# DDR3L.net
KiCad netlist of a schematic drawn in Altium Designer
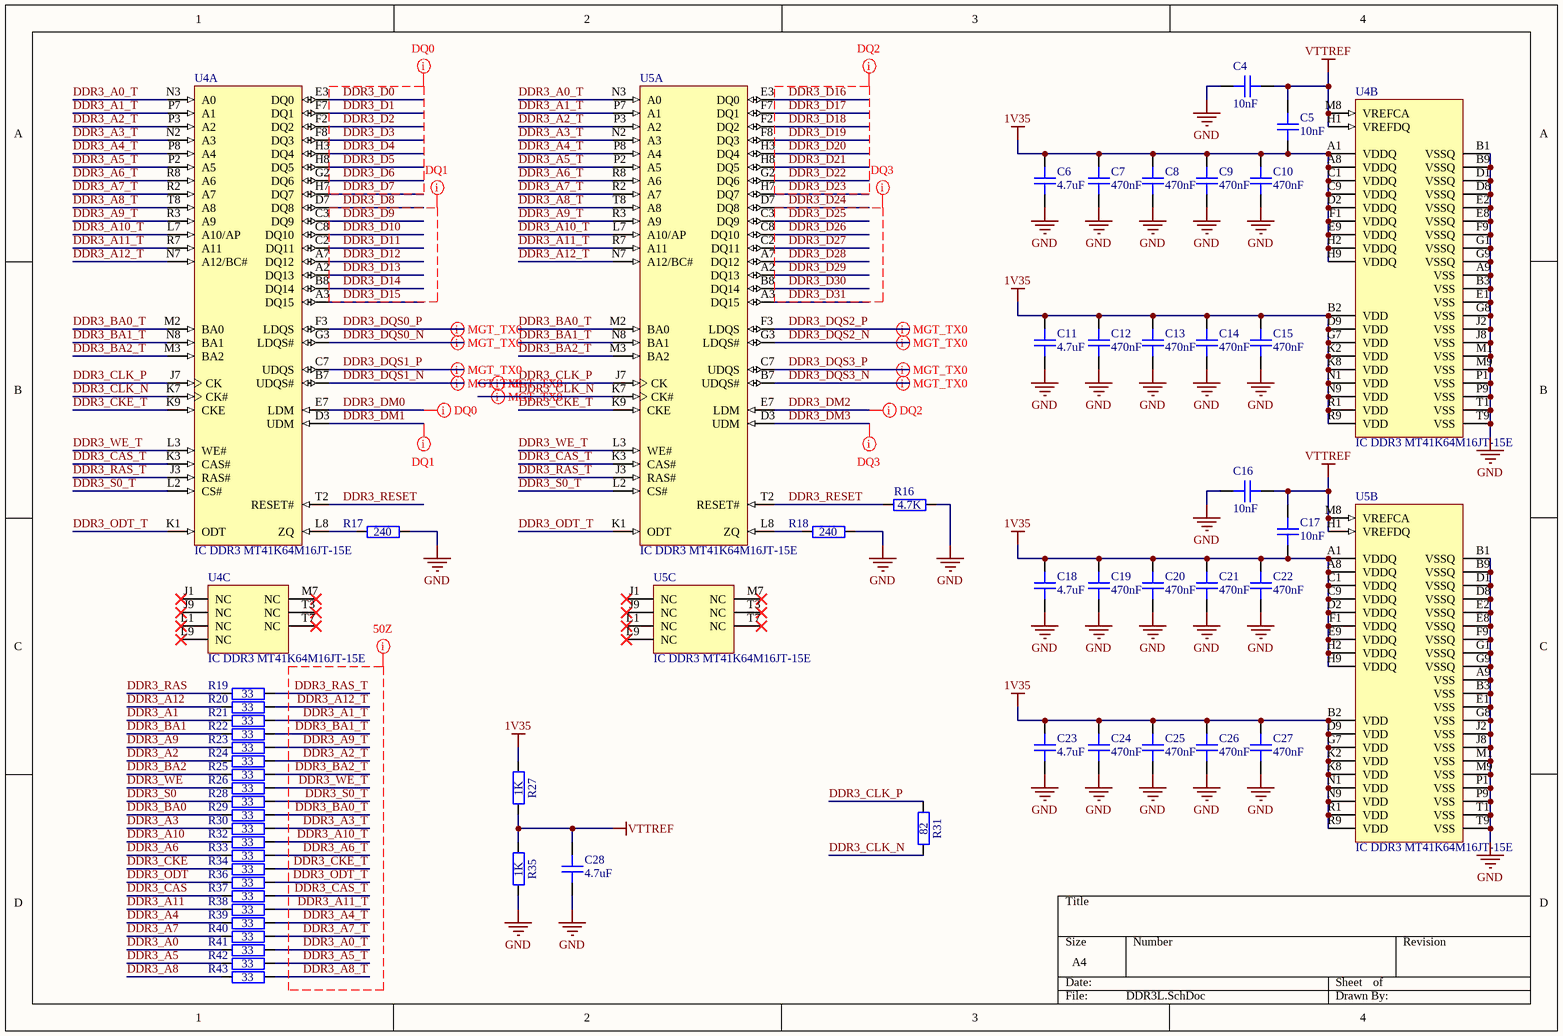
[diagram p0: DDR3L.SchDoc]

(export (version "E")
  (design (tool "Eeschema 10.0.6"))
  (components
    (comp (ref "C4")
      (value "10nF")
      (footprint "GEN_C_0402")
      (fields
        (field (name "HOUSE PART NUMBER") "C-10nF-0402-002")
        (field (name "MANUFACTURER") "Murata")
        (field (name "MANUFACTURER PART NUMBER") "GRM155R71H103KA88J")
      )
      (libsource (lib "DSO") (part "CAP 10nF 50V X7R 0402"))
    )
    (comp (ref "C5")
      (value "10nF")
      (footprint "GEN_C_0402")
      (fields
        (field (name "HOUSE PART NUMBER") "C-10nF-0402-002")
        (field (name "MANUFACTURER") "Murata")
        (field (name "MANUFACTURER PART NUMBER") "GRM155R71H103KA88J")
      )
      (libsource (lib "DSO") (part "CAP 10nF 50V X7R 0402"))
    )
    (comp (ref "C6")
      (value "4.7uF")
      (footprint "GEN_C_0402")
      (fields
        (field (name "HOUSE PART NUMBER") "C-4.7uF-0402-002")
        (field (name "MANUFACTURER") "Murata")
        (field (name "MANUFACTURER PART NUMBER") "GRM155R60J475ME47D")
      )
      (libsource (lib "DSO") (part "CAP 4.7uF 6.3V X5R 0402"))
    )
    (comp (ref "C7")
      (value "470nF")
      (footprint "GEN_C_0201")
      (fields
        (field (name "HOUSE PART NUMBER") "C-470nF-0201-002")
        (field (name "MANUFACTURER") "Murata")
        (field (name "MANUFACTURER PART NUMBER") "GRM033R60J474KE90D")
      )
      (libsource (lib "DSO") (part "CAP 470nF 6.3V X5R 0201"))
    )
    (comp (ref "C8")
      (value "470nF")
      (footprint "GEN_C_0201")
      (fields
        (field (name "HOUSE PART NUMBER") "C-470nF-0201-002")
        (field (name "MANUFACTURER") "Murata")
        (field (name "MANUFACTURER PART NUMBER") "GRM033R60J474KE90D")
      )
      (libsource (lib "DSO") (part "CAP 470nF 6.3V X5R 0201"))
    )
    (comp (ref "C9")
      (value "470nF")
      (footprint "GEN_C_0201")
      (fields
        (field (name "HOUSE PART NUMBER") "C-470nF-0201-002")
        (field (name "MANUFACTURER") "Murata")
        (field (name "MANUFACTURER PART NUMBER") "GRM033R60J474KE90D")
      )
      (libsource (lib "DSO") (part "CAP 470nF 6.3V X5R 0201"))
    )
    (comp (ref "C10")
      (value "470nF")
      (footprint "GEN_C_0201")
      (fields
        (field (name "HOUSE PART NUMBER") "C-470nF-0201-002")
        (field (name "MANUFACTURER") "Murata")
        (field (name "MANUFACTURER PART NUMBER") "GRM033R60J474KE90D")
      )
      (libsource (lib "DSO") (part "CAP 470nF 6.3V X5R 0201"))
    )
    (comp (ref "C11")
      (value "4.7uF")
      (footprint "GEN_C_0402")
      (fields
        (field (name "HOUSE PART NUMBER") "C-4.7uF-0402-002")
        (field (name "MANUFACTURER") "Murata")
        (field (name "MANUFACTURER PART NUMBER") "GRM155R60J475ME47D")
      )
      (libsource (lib "DSO") (part "CAP 4.7uF 6.3V X5R 0402"))
    )
    (comp (ref "C12")
      (value "470nF")
      (footprint "GEN_C_0201")
      (fields
        (field (name "HOUSE PART NUMBER") "C-470nF-0201-002")
        (field (name "MANUFACTURER") "Murata")
        (field (name "MANUFACTURER PART NUMBER") "GRM033R60J474KE90D")
      )
      (libsource (lib "DSO") (part "CAP 470nF 6.3V X5R 0201"))
    )
    (comp (ref "C13")
      (value "470nF")
      (footprint "GEN_C_0201")
      (fields
        (field (name "HOUSE PART NUMBER") "C-470nF-0201-002")
        (field (name "MANUFACTURER") "Murata")
        (field (name "MANUFACTURER PART NUMBER") "GRM033R60J474KE90D")
      )
      (libsource (lib "DSO") (part "CAP 470nF 6.3V X5R 0201"))
    )
    (comp (ref "C14")
      (value "470nF")
      (footprint "GEN_C_0201")
      (fields
        (field (name "HOUSE PART NUMBER") "C-470nF-0201-002")
        (field (name "MANUFACTURER") "Murata")
        (field (name "MANUFACTURER PART NUMBER") "GRM033R60J474KE90D")
      )
      (libsource (lib "DSO") (part "CAP 470nF 6.3V X5R 0201"))
    )
    (comp (ref "C15")
      (value "470nF")
      (footprint "GEN_C_0201")
      (fields
        (field (name "HOUSE PART NUMBER") "C-470nF-0201-002")
        (field (name "MANUFACTURER") "Murata")
        (field (name "MANUFACTURER PART NUMBER") "GRM033R60J474KE90D")
      )
      (libsource (lib "DSO") (part "CAP 470nF 6.3V X5R 0201"))
    )
    (comp (ref "C16")
      (value "10nF")
      (footprint "GEN_C_0402")
      (fields
        (field (name "HOUSE PART NUMBER") "C-10nF-0402-002")
        (field (name "MANUFACTURER") "Murata")
        (field (name "MANUFACTURER PART NUMBER") "GRM155R71H103KA88J")
      )
      (libsource (lib "DSO") (part "CAP 10nF 50V X7R 0402"))
    )
    (comp (ref "C17")
      (value "10nF")
      (footprint "GEN_C_0402")
      (fields
        (field (name "HOUSE PART NUMBER") "C-10nF-0402-002")
        (field (name "MANUFACTURER") "Murata")
        (field (name "MANUFACTURER PART NUMBER") "GRM155R71H103KA88J")
      )
      (libsource (lib "DSO") (part "CAP 10nF 50V X7R 0402"))
    )
    (comp (ref "C18")
      (value "4.7uF")
      (footprint "GEN_C_0402")
      (fields
        (field (name "HOUSE PART NUMBER") "C-4.7uF-0402-002")
        (field (name "MANUFACTURER") "Murata")
        (field (name "MANUFACTURER PART NUMBER") "GRM155R60J475ME47D")
      )
      (libsource (lib "DSO") (part "CAP 4.7uF 6.3V X5R 0402"))
    )
    (comp (ref "C19")
      (value "470nF")
      (footprint "GEN_C_0201")
      (fields
        (field (name "HOUSE PART NUMBER") "C-470nF-0201-002")
        (field (name "MANUFACTURER") "Murata")
        (field (name "MANUFACTURER PART NUMBER") "GRM033R60J474KE90D")
      )
      (libsource (lib "DSO") (part "CAP 470nF 6.3V X5R 0201"))
    )
    (comp (ref "C20")
      (value "470nF")
      (footprint "GEN_C_0201")
      (fields
        (field (name "HOUSE PART NUMBER") "C-470nF-0201-002")
        (field (name "MANUFACTURER") "Murata")
        (field (name "MANUFACTURER PART NUMBER") "GRM033R60J474KE90D")
      )
      (libsource (lib "DSO") (part "CAP 470nF 6.3V X5R 0201"))
    )
    (comp (ref "C21")
      (value "470nF")
      (footprint "GEN_C_0201")
      (fields
        (field (name "HOUSE PART NUMBER") "C-470nF-0201-002")
        (field (name "MANUFACTURER") "Murata")
        (field (name "MANUFACTURER PART NUMBER") "GRM033R60J474KE90D")
      )
      (libsource (lib "DSO") (part "CAP 470nF 6.3V X5R 0201"))
    )
    (comp (ref "C22")
      (value "470nF")
      (footprint "GEN_C_0201")
      (fields
        (field (name "HOUSE PART NUMBER") "C-470nF-0201-002")
        (field (name "MANUFACTURER") "Murata")
        (field (name "MANUFACTURER PART NUMBER") "GRM033R60J474KE90D")
      )
      (libsource (lib "DSO") (part "CAP 470nF 6.3V X5R 0201"))
    )
    (comp (ref "C23")
      (value "4.7uF")
      (footprint "GEN_C_0402")
      (fields
        (field (name "HOUSE PART NUMBER") "C-4.7uF-0402-002")
        (field (name "MANUFACTURER") "Murata")
        (field (name "MANUFACTURER PART NUMBER") "GRM155R60J475ME47D")
      )
      (libsource (lib "DSO") (part "CAP 4.7uF 6.3V X5R 0402"))
    )
    (comp (ref "C24")
      (value "470nF")
      (footprint "GEN_C_0201")
      (fields
        (field (name "HOUSE PART NUMBER") "C-470nF-0201-002")
        (field (name "MANUFACTURER") "Murata")
        (field (name "MANUFACTURER PART NUMBER") "GRM033R60J474KE90D")
      )
      (libsource (lib "DSO") (part "CAP 470nF 6.3V X5R 0201"))
    )
    (comp (ref "C25")
      (value "470nF")
      (footprint "GEN_C_0201")
      (fields
        (field (name "HOUSE PART NUMBER") "C-470nF-0201-002")
        (field (name "MANUFACTURER") "Murata")
        (field (name "MANUFACTURER PART NUMBER") "GRM033R60J474KE90D")
      )
      (libsource (lib "DSO") (part "CAP 470nF 6.3V X5R 0201"))
    )
    (comp (ref "C26")
      (value "470nF")
      (footprint "GEN_C_0201")
      (fields
        (field (name "HOUSE PART NUMBER") "C-470nF-0201-002")
        (field (name "MANUFACTURER") "Murata")
        (field (name "MANUFACTURER PART NUMBER") "GRM033R60J474KE90D")
      )
      (libsource (lib "DSO") (part "CAP 470nF 6.3V X5R 0201"))
    )
    (comp (ref "C27")
      (value "470nF")
      (footprint "GEN_C_0201")
      (fields
        (field (name "HOUSE PART NUMBER") "C-470nF-0201-002")
        (field (name "MANUFACTURER") "Murata")
        (field (name "MANUFACTURER PART NUMBER") "GRM033R60J474KE90D")
      )
      (libsource (lib "DSO") (part "CAP 470nF 6.3V X5R 0201"))
    )
    (comp (ref "C28")
      (value "4.7uF")
      (footprint "GEN_C_0402")
      (fields
        (field (name "HOUSE PART NUMBER") "C-4.7uF-0402-002")
        (field (name "MANUFACTURER") "Murata")
        (field (name "MANUFACTURER PART NUMBER") "GRM155R60J475ME47D")
      )
      (libsource (lib "DSO") (part "CAP 4.7uF 6.3V X5R 0402"))
    )
    (comp (ref "R16")
      (value "4.7K")
      (footprint "GEN_R_0201")
      (fields
        (field (name "TOLERANCE") "1%")
        (field (name "HOUSE PART NUMBER") "R-4.7K-0201-1%-001")
        (field (name "MANUFACTURER") "Yageo")
      )
      (libsource (lib "DSO") (part "RES 4.7K OHM 1% 1/20W 0201"))
    )
    (comp (ref "R17")
      (value "240")
      (footprint "GEN_R_0402")
      (fields
        (field (name "TOLERANCE") "1%")
        (field (name "HOUSE PART NUMBER") "R-240-0402-1%-001")
        (field (name "MANUFACTURER") "Yageo")
      )
      (libsource (lib "DSO") (part "RES 240 OHM 1% 1/16W 0402"))
    )
    (comp (ref "R18")
      (value "240")
      (footprint "GEN_R_0402")
      (fields
        (field (name "TOLERANCE") "1%")
        (field (name "HOUSE PART NUMBER") "R-240-0402-1%-001")
        (field (name "MANUFACTURER") "Yageo")
      )
      (libsource (lib "DSO") (part "RES 240 OHM 1% 1/16W 0402"))
    )
    (comp (ref "R19")
      (value "33")
      (footprint "GEN_R_0201")
      (fields
        (field (name "TOLERANCE") "1%")
        (field (name "HOUSE PART NUMBER") "R-33-0201-1%-001")
        (field (name "MANUFACTURER") "Stackpole Electronics")
      )
      (libsource (lib "DSO") (part "RES 33 OHM 1% 1/20W 0201"))
    )
    (comp (ref "R20")
      (value "33")
      (footprint "GEN_R_0201")
      (fields
        (field (name "TOLERANCE") "1%")
        (field (name "HOUSE PART NUMBER") "R-33-0201-1%-001")
        (field (name "MANUFACTURER") "Stackpole Electronics")
      )
      (libsource (lib "DSO") (part "RES 33 OHM 1% 1/20W 0201"))
    )
    (comp (ref "R21")
      (value "33")
      (footprint "GEN_R_0201")
      (fields
        (field (name "TOLERANCE") "1%")
        (field (name "HOUSE PART NUMBER") "R-33-0201-1%-001")
        (field (name "MANUFACTURER") "Stackpole Electronics")
      )
      (libsource (lib "DSO") (part "RES 33 OHM 1% 1/20W 0201"))
    )
    (comp (ref "R22")
      (value "33")
      (footprint "GEN_R_0201")
      (fields
        (field (name "TOLERANCE") "1%")
        (field (name "HOUSE PART NUMBER") "R-33-0201-1%-001")
        (field (name "MANUFACTURER") "Stackpole Electronics")
      )
      (libsource (lib "DSO") (part "RES 33 OHM 1% 1/20W 0201"))
    )
    (comp (ref "R23")
      (value "33")
      (footprint "GEN_R_0201")
      (fields
        (field (name "TOLERANCE") "1%")
        (field (name "HOUSE PART NUMBER") "R-33-0201-1%-001")
        (field (name "MANUFACTURER") "Stackpole Electronics")
      )
      (libsource (lib "DSO") (part "RES 33 OHM 1% 1/20W 0201"))
    )
    (comp (ref "R24")
      (value "33")
      (footprint "GEN_R_0201")
      (fields
        (field (name "TOLERANCE") "1%")
        (field (name "HOUSE PART NUMBER") "R-33-0201-1%-001")
        (field (name "MANUFACTURER") "Stackpole Electronics")
      )
      (libsource (lib "DSO") (part "RES 33 OHM 1% 1/20W 0201"))
    )
    (comp (ref "R25")
      (value "33")
      (footprint "GEN_R_0201")
      (fields
        (field (name "TOLERANCE") "1%")
        (field (name "HOUSE PART NUMBER") "R-33-0201-1%-001")
        (field (name "MANUFACTURER") "Stackpole Electronics")
      )
      (libsource (lib "DSO") (part "RES 33 OHM 1% 1/20W 0201"))
    )
    (comp (ref "R26")
      (value "33")
      (footprint "GEN_R_0201")
      (fields
        (field (name "TOLERANCE") "1%")
        (field (name "HOUSE PART NUMBER") "R-33-0201-1%-001")
        (field (name "MANUFACTURER") "Stackpole Electronics")
      )
      (libsource (lib "DSO") (part "RES 33 OHM 1% 1/20W 0201"))
    )
    (comp (ref "R27")
      (value "1K")
      (footprint "GEN_R_0402")
      (fields
        (field (name "TOLERANCE") "1%")
        (field (name "HOUSE PART NUMBER") "R-1K-0402-1%-001")
        (field (name "MANUFACTURER") "Yageo")
      )
      (libsource (lib "DSO") (part "RES 1K OHM 1% 1/10W 0402"))
    )
    (comp (ref "R28")
      (value "33")
      (footprint "GEN_R_0201")
      (fields
        (field (name "TOLERANCE") "1%")
        (field (name "HOUSE PART NUMBER") "R-33-0201-1%-001")
        (field (name "MANUFACTURER") "Stackpole Electronics")
      )
      (libsource (lib "DSO") (part "RES 33 OHM 1% 1/20W 0201"))
    )
    (comp (ref "R29")
      (value "33")
      (footprint "GEN_R_0201")
      (fields
        (field (name "TOLERANCE") "1%")
        (field (name "HOUSE PART NUMBER") "R-33-0201-1%-001")
        (field (name "MANUFACTURER") "Stackpole Electronics")
      )
      (libsource (lib "DSO") (part "RES 33 OHM 1% 1/20W 0201"))
    )
    (comp (ref "R30")
      (value "33")
      (footprint "GEN_R_0201")
      (fields
        (field (name "TOLERANCE") "1%")
        (field (name "HOUSE PART NUMBER") "R-33-0201-1%-001")
        (field (name "MANUFACTURER") "Stackpole Electronics")
      )
      (libsource (lib "DSO") (part "RES 33 OHM 1% 1/20W 0201"))
    )
    (comp (ref "R31")
      (value "82")
      (footprint "GEN_R_0402")
      (fields
        (field (name "TOLERANCE") "1%")
        (field (name "HOUSE PART NUMBER") "R-82-0402-1%-001")
        (field (name "MANUFACTURER") "Yageo")
      )
      (libsource (lib "DSO") (part "RES 82 OHM 1% 1/16W 0402"))
    )
    (comp (ref "R32")
      (value "33")
      (footprint "GEN_R_0201")
      (fields
        (field (name "TOLERANCE") "1%")
        (field (name "HOUSE PART NUMBER") "R-33-0201-1%-001")
        (field (name "MANUFACTURER") "Stackpole Electronics")
      )
      (libsource (lib "DSO") (part "RES 33 OHM 1% 1/20W 0201"))
    )
    (comp (ref "R33")
      (value "33")
      (footprint "GEN_R_0201")
      (fields
        (field (name "TOLERANCE") "1%")
        (field (name "HOUSE PART NUMBER") "R-33-0201-1%-001")
        (field (name "MANUFACTURER") "Stackpole Electronics")
      )
      (libsource (lib "DSO") (part "RES 33 OHM 1% 1/20W 0201"))
    )
    (comp (ref "R34")
      (value "33")
      (footprint "GEN_R_0201")
      (fields
        (field (name "TOLERANCE") "1%")
        (field (name "HOUSE PART NUMBER") "R-33-0201-1%-001")
        (field (name "MANUFACTURER") "Stackpole Electronics")
      )
      (libsource (lib "DSO") (part "RES 33 OHM 1% 1/20W 0201"))
    )
    (comp (ref "R35")
      (value "1K")
      (footprint "GEN_R_0402")
      (fields
        (field (name "TOLERANCE") "1%")
        (field (name "HOUSE PART NUMBER") "R-1K-0402-1%-001")
        (field (name "MANUFACTURER") "Yageo")
      )
      (libsource (lib "DSO") (part "RES 1K OHM 1% 1/10W 0402"))
    )
    (comp (ref "R36")
      (value "33")
      (footprint "GEN_R_0201")
      (fields
        (field (name "TOLERANCE") "1%")
        (field (name "HOUSE PART NUMBER") "R-33-0201-1%-001")
        (field (name "MANUFACTURER") "Stackpole Electronics")
      )
      (libsource (lib "DSO") (part "RES 33 OHM 1% 1/20W 0201"))
    )
    (comp (ref "R37")
      (value "33")
      (footprint "GEN_R_0201")
      (fields
        (field (name "TOLERANCE") "1%")
        (field (name "HOUSE PART NUMBER") "R-33-0201-1%-001")
        (field (name "MANUFACTURER") "Stackpole Electronics")
      )
      (libsource (lib "DSO") (part "RES 33 OHM 1% 1/20W 0201"))
    )
    (comp (ref "R38")
      (value "33")
      (footprint "GEN_R_0201")
      (fields
        (field (name "TOLERANCE") "1%")
        (field (name "HOUSE PART NUMBER") "R-33-0201-1%-001")
        (field (name "MANUFACTURER") "Stackpole Electronics")
      )
      (libsource (lib "DSO") (part "RES 33 OHM 1% 1/20W 0201"))
    )
    (comp (ref "R39")
      (value "33")
      (footprint "GEN_R_0201")
      (fields
        (field (name "TOLERANCE") "1%")
        (field (name "HOUSE PART NUMBER") "R-33-0201-1%-001")
        (field (name "MANUFACTURER") "Stackpole Electronics")
      )
      (libsource (lib "DSO") (part "RES 33 OHM 1% 1/20W 0201"))
    )
    (comp (ref "R40")
      (value "33")
      (footprint "GEN_R_0201")
      (fields
        (field (name "TOLERANCE") "1%")
        (field (name "HOUSE PART NUMBER") "R-33-0201-1%-001")
        (field (name "MANUFACTURER") "Stackpole Electronics")
      )
      (libsource (lib "DSO") (part "RES 33 OHM 1% 1/20W 0201"))
    )
    (comp (ref "R41")
      (value "33")
      (footprint "GEN_R_0201")
      (fields
        (field (name "TOLERANCE") "1%")
        (field (name "HOUSE PART NUMBER") "R-33-0201-1%-001")
        (field (name "MANUFACTURER") "Stackpole Electronics")
      )
      (libsource (lib "DSO") (part "RES 33 OHM 1% 1/20W 0201"))
    )
    (comp (ref "R42")
      (value "33")
      (footprint "GEN_R_0201")
      (fields
        (field (name "TOLERANCE") "1%")
        (field (name "HOUSE PART NUMBER") "R-33-0201-1%-001")
        (field (name "MANUFACTURER") "Stackpole Electronics")
      )
      (libsource (lib "DSO") (part "RES 33 OHM 1% 1/20W 0201"))
    )
    (comp (ref "R43")
      (value "33")
      (footprint "GEN_R_0201")
      (fields
        (field (name "TOLERANCE") "1%")
        (field (name "HOUSE PART NUMBER") "R-33-0201-1%-001")
        (field (name "MANUFACTURER") "Stackpole Electronics")
      )
      (libsource (lib "DSO") (part "RES 33 OHM 1% 1/20W 0201"))
    )
    (comp (ref "U4")
      (value "IC DDR3 MT41K64M16JT-15E")
      (footprint "MICT-JT-96")
      (description "1Gb DDR3-1333 SDRAM, 64Mb x 16, 1.5ns, 1.35V, 0 to 95 degC, 96-Ball FBGA, Pb-Free")
      (fields (field (name "MANUFACTURER") "Micron") (field (name "HOUSE PART NUMBER") "MT41K64M16TW-107:J"))
      (libsource (lib "DSO") (part "IC DDR3 MT41K64M16JT-15E"))
    )
    (comp (ref "U5")
      (value "IC DDR3 MT41K64M16JT-15E")
      (footprint "MICT-JT-96")
      (description "1Gb DDR3-1333 SDRAM, 64Mb x 16, 1.5ns, 1.35V, 0 to 95 degC, 96-Ball FBGA, Pb-Free")
      (fields (field (name "MANUFACTURER") "Micron") (field (name "HOUSE PART NUMBER") "MT41K64M16TW-107:J"))
      (libsource (lib "DSO") (part "IC DDR3 MT41K64M16JT-15E"))
    )
  )
  (nets
    (net (code "1") (name "/DDR3_A0") (class "Default")
      (node (ref "R41") (pin "1") (pinfunction "1_1") (pintype "passive"))
    )
    (net (code "2") (name "/DDR3_A0_T") (class "Default")
      (node (ref "R41") (pin "2") (pinfunction "2_2") (pintype "passive"))
      (node (ref "U4") (pin "N3") (pinfunction "A0_N3") (pintype "input"))
      (node (ref "U5") (pin "N3") (pinfunction "A0_N3") (pintype "input"))
    )
    (net (code "3") (name "/DDR3_A1") (class "Default")
      (node (ref "R21") (pin "1") (pinfunction "1_1") (pintype "passive"))
    )
    (net (code "4") (name "/DDR3_A1_T") (class "Default")
      (node (ref "R21") (pin "2") (pinfunction "2_2") (pintype "passive"))
      (node (ref "U4") (pin "P7") (pinfunction "A1_P7") (pintype "input"))
      (node (ref "U5") (pin "P7") (pinfunction "A1_P7") (pintype "input"))
    )
    (net (code "5") (name "/DDR3_A2") (class "Default")
      (node (ref "R24") (pin "1") (pinfunction "1_1") (pintype "passive"))
    )
    (net (code "6") (name "/DDR3_A2_T") (class "Default")
      (node (ref "R24") (pin "2") (pinfunction "2_2") (pintype "passive"))
      (node (ref "U4") (pin "P3") (pinfunction "A2_P3") (pintype "input"))
      (node (ref "U5") (pin "P3") (pinfunction "A2_P3") (pintype "input"))
    )
    (net (code "7") (name "/DDR3_A3") (class "Default")
      (node (ref "R30") (pin "1") (pinfunction "1_1") (pintype "passive"))
    )
    (net (code "8") (name "/DDR3_A3_T") (class "Default")
      (node (ref "R30") (pin "2") (pinfunction "2_2") (pintype "passive"))
      (node (ref "U4") (pin "N2") (pinfunction "A3_N2") (pintype "input"))
      (node (ref "U5") (pin "N2") (pinfunction "A3_N2") (pintype "input"))
    )
    (net (code "9") (name "/DDR3_A4") (class "Default")
      (node (ref "R39") (pin "1") (pinfunction "1_1") (pintype "passive"))
    )
    (net (code "10") (name "/DDR3_A4_T") (class "Default")
      (node (ref "R39") (pin "2") (pinfunction "2_2") (pintype "passive"))
      (node (ref "U4") (pin "P8") (pinfunction "A4_P8") (pintype "input"))
      (node (ref "U5") (pin "P8") (pinfunction "A4_P8") (pintype "input"))
    )
    (net (code "11") (name "/DDR3_A5") (class "Default")
      (node (ref "R42") (pin "1") (pinfunction "1_1") (pintype "passive"))
    )
    (net (code "12") (name "/DDR3_A5_T") (class "Default")
      (node (ref "R42") (pin "2") (pinfunction "2_2") (pintype "passive"))
      (node (ref "U4") (pin "P2") (pinfunction "A5_P2") (pintype "input"))
      (node (ref "U5") (pin "P2") (pinfunction "A5_P2") (pintype "input"))
    )
    (net (code "13") (name "/DDR3_A6") (class "Default")
      (node (ref "R33") (pin "1") (pinfunction "1_1") (pintype "passive"))
    )
    (net (code "14") (name "/DDR3_A6_T") (class "Default")
      (node (ref "R33") (pin "2") (pinfunction "2_2") (pintype "passive"))
      (node (ref "U4") (pin "R8") (pinfunction "A6_R8") (pintype "input"))
      (node (ref "U5") (pin "R8") (pinfunction "A6_R8") (pintype "input"))
    )
    (net (code "15") (name "/DDR3_A7") (class "Default")
      (node (ref "R40") (pin "1") (pinfunction "1_1") (pintype "passive"))
    )
    (net (code "16") (name "/DDR3_A7_T") (class "Default")
      (node (ref "R40") (pin "2") (pinfunction "2_2") (pintype "passive"))
      (node (ref "U4") (pin "R2") (pinfunction "A7_R2") (pintype "input"))
      (node (ref "U5") (pin "R2") (pinfunction "A7_R2") (pintype "input"))
    )
    (net (code "17") (name "/DDR3_A8") (class "Default")
      (node (ref "R43") (pin "1") (pinfunction "1_1") (pintype "passive"))
    )
    (net (code "18") (name "/DDR3_A8_T") (class "Default")
      (node (ref "R43") (pin "2") (pinfunction "2_2") (pintype "passive"))
      (node (ref "U4") (pin "T8") (pinfunction "A8_T8") (pintype "input"))
      (node (ref "U5") (pin "T8") (pinfunction "A8_T8") (pintype "input"))
    )
    (net (code "19") (name "/DDR3_A9") (class "Default")
      (node (ref "R23") (pin "1") (pinfunction "1_1") (pintype "passive"))
    )
    (net (code "20") (name "/DDR3_A9_T") (class "Default")
      (node (ref "R23") (pin "2") (pinfunction "2_2") (pintype "passive"))
      (node (ref "U4") (pin "R3") (pinfunction "A9_R3") (pintype "input"))
      (node (ref "U5") (pin "R3") (pinfunction "A9_R3") (pintype "input"))
    )
    (net (code "21") (name "/DDR3_A10") (class "Default")
      (node (ref "R32") (pin "1") (pinfunction "1_1") (pintype "passive"))
    )
    (net (code "22") (name "/DDR3_A10_T") (class "Default")
      (node (ref "R32") (pin "2") (pinfunction "2_2") (pintype "passive"))
      (node (ref "U4") (pin "L7") (pinfunction "A10/AP_L7") (pintype "input"))
      (node (ref "U5") (pin "L7") (pinfunction "A10/AP_L7") (pintype "input"))
    )
    (net (code "23") (name "/DDR3_A11") (class "Default")
      (node (ref "R38") (pin "1") (pinfunction "1_1") (pintype "passive"))
    )
    (net (code "24") (name "/DDR3_A11_T") (class "Default")
      (node (ref "R38") (pin "2") (pinfunction "2_2") (pintype "passive"))
      (node (ref "U4") (pin "R7") (pinfunction "A11_R7") (pintype "input"))
      (node (ref "U5") (pin "R7") (pinfunction "A11_R7") (pintype "input"))
    )
    (net (code "25") (name "/DDR3_A12") (class "Default")
      (node (ref "R20") (pin "1") (pinfunction "1_1") (pintype "passive"))
    )
    (net (code "26") (name "/DDR3_A12_T") (class "Default")
      (node (ref "R20") (pin "2") (pinfunction "2_2") (pintype "passive"))
      (node (ref "U4") (pin "N7") (pinfunction "A12/BC#_N7") (pintype "input"))
      (node (ref "U5") (pin "N7") (pinfunction "A12/BC#_N7") (pintype "input"))
    )
    (net (code "27") (name "/DDR3_BA0") (class "Default")
      (node (ref "R29") (pin "1") (pinfunction "1_1") (pintype "passive"))
    )
    (net (code "28") (name "/DDR3_BA0_T") (class "Default")
      (node (ref "R29") (pin "2") (pinfunction "2_2") (pintype "passive"))
      (node (ref "U4") (pin "M2") (pinfunction "BA0_M2") (pintype "input"))
      (node (ref "U5") (pin "M2") (pinfunction "BA0_M2") (pintype "input"))
    )
    (net (code "29") (name "/DDR3_BA1") (class "Default")
      (node (ref "R22") (pin "1") (pinfunction "1_1") (pintype "passive"))
    )
    (net (code "30") (name "/DDR3_BA1_T") (class "Default")
      (node (ref "R22") (pin "2") (pinfunction "2_2") (pintype "passive"))
      (node (ref "U4") (pin "N8") (pinfunction "BA1_N8") (pintype "input"))
      (node (ref "U5") (pin "N8") (pinfunction "BA1_N8") (pintype "input"))
    )
    (net (code "31") (name "/DDR3_BA2") (class "Default")
      (node (ref "R25") (pin "1") (pinfunction "1_1") (pintype "passive"))
    )
    (net (code "32") (name "/DDR3_BA2_T") (class "Default")
      (node (ref "R25") (pin "2") (pinfunction "2_2") (pintype "passive"))
      (node (ref "U4") (pin "M3") (pinfunction "BA2_M3") (pintype "input"))
      (node (ref "U5") (pin "M3") (pinfunction "BA2_M3") (pintype "input"))
    )
    (net (code "33") (name "/DDR3_CAS") (class "Default")
      (node (ref "R37") (pin "1") (pinfunction "1_1") (pintype "passive"))
    )
    (net (code "34") (name "/DDR3_CAS_T") (class "Default")
      (node (ref "R37") (pin "2") (pinfunction "2_2") (pintype "passive"))
      (node (ref "U4") (pin "K3") (pinfunction "CAS#_K3") (pintype "input"))
      (node (ref "U5") (pin "K3") (pinfunction "CAS#_K3") (pintype "input"))
    )
    (net (code "35") (name "/DDR3_CKE") (class "Default")
      (node (ref "R34") (pin "1") (pinfunction "1_1") (pintype "passive"))
    )
    (net (code "36") (name "/DDR3_CKE_T") (class "Default")
      (node (ref "R34") (pin "2") (pinfunction "2_2") (pintype "passive"))
      (node (ref "U4") (pin "K9") (pinfunction "CKE_K9") (pintype "input"))
      (node (ref "U5") (pin "K9") (pinfunction "CKE_K9") (pintype "input"))
    )
    (net (code "37") (name "/DDR3_CLK_N") (class "Default")
      (node (ref "R31") (pin "1") (pinfunction "1_1") (pintype "passive"))
      (node (ref "U4") (pin "K7") (pinfunction "CK#_K7") (pintype "input"))
      (node (ref "U5") (pin "K7") (pinfunction "CK#_K7") (pintype "input"))
    )
    (net (code "38") (name "/DDR3_CLK_P") (class "Default")
      (node (ref "R31") (pin "2") (pinfunction "2_2") (pintype "passive"))
      (node (ref "U4") (pin "J7") (pinfunction "CK_J7") (pintype "input"))
      (node (ref "U5") (pin "J7") (pinfunction "CK_J7") (pintype "input"))
    )
    (net (code "39") (name "/DDR3_D0") (class "Default")
      (node (ref "U4") (pin "E3") (pinfunction "DQ0_E3") (pintype "bidirectional"))
    )
    (net (code "40") (name "/DDR3_D1") (class "Default")
      (node (ref "U4") (pin "F7") (pinfunction "DQ1_F7") (pintype "bidirectional"))
    )
    (net (code "41") (name "/DDR3_D2") (class "Default")
      (node (ref "U4") (pin "F2") (pinfunction "DQ2_F2") (pintype "bidirectional"))
    )
    (net (code "42") (name "/DDR3_D3") (class "Default")
      (node (ref "U4") (pin "F8") (pinfunction "DQ3_F8") (pintype "bidirectional"))
    )
    (net (code "43") (name "/DDR3_D4") (class "Default")
      (node (ref "U4") (pin "H3") (pinfunction "DQ4_H3") (pintype "bidirectional"))
    )
    (net (code "44") (name "/DDR3_D5") (class "Default")
      (node (ref "U4") (pin "H8") (pinfunction "DQ5_H8") (pintype "bidirectional"))
    )
    (net (code "45") (name "/DDR3_D6") (class "Default")
      (node (ref "U4") (pin "G2") (pinfunction "DQ6_G2") (pintype "bidirectional"))
    )
    (net (code "46") (name "/DDR3_D7") (class "Default")
      (node (ref "U4") (pin "H7") (pinfunction "DQ7_H7") (pintype "bidirectional"))
    )
    (net (code "47") (name "/DDR3_D8") (class "Default")
      (node (ref "U4") (pin "D7") (pinfunction "DQ8_D7") (pintype "bidirectional"))
    )
    (net (code "48") (name "/DDR3_D9") (class "Default")
      (node (ref "U4") (pin "C3") (pinfunction "DQ9_C3") (pintype "bidirectional"))
    )
    (net (code "49") (name "/DDR3_D10") (class "Default")
      (node (ref "U4") (pin "C8") (pinfunction "DQ10_C8") (pintype "bidirectional"))
    )
    (net (code "50") (name "/DDR3_D11") (class "Default")
      (node (ref "U4") (pin "C2") (pinfunction "DQ11_C2") (pintype "bidirectional"))
    )
    (net (code "51") (name "/DDR3_D12") (class "Default")
      (node (ref "U4") (pin "A7") (pinfunction "DQ12_A7") (pintype "bidirectional"))
    )
    (net (code "52") (name "/DDR3_D13") (class "Default")
      (node (ref "U4") (pin "A2") (pinfunction "DQ13_A2") (pintype "bidirectional"))
    )
    (net (code "53") (name "/DDR3_D14") (class "Default")
      (node (ref "U4") (pin "B8") (pinfunction "DQ14_B8") (pintype "bidirectional"))
    )
    (net (code "54") (name "/DDR3_D15") (class "Default")
      (node (ref "U4") (pin "A3") (pinfunction "DQ15_A3") (pintype "bidirectional"))
    )
    (net (code "55") (name "/DDR3_D16") (class "Default")
      (node (ref "U5") (pin "E3") (pinfunction "DQ0_E3") (pintype "bidirectional"))
    )
    (net (code "56") (name "/DDR3_D17") (class "Default")
      (node (ref "U5") (pin "F7") (pinfunction "DQ1_F7") (pintype "bidirectional"))
    )
    (net (code "57") (name "/DDR3_D18") (class "Default")
      (node (ref "U5") (pin "F2") (pinfunction "DQ2_F2") (pintype "bidirectional"))
    )
    (net (code "58") (name "/DDR3_D19") (class "Default")
      (node (ref "U5") (pin "F8") (pinfunction "DQ3_F8") (pintype "bidirectional"))
    )
    (net (code "59") (name "/DDR3_D20") (class "Default")
      (node (ref "U5") (pin "H3") (pinfunction "DQ4_H3") (pintype "bidirectional"))
    )
    (net (code "60") (name "/DDR3_D21") (class "Default")
      (node (ref "U5") (pin "H8") (pinfunction "DQ5_H8") (pintype "bidirectional"))
    )
    (net (code "61") (name "/DDR3_D22") (class "Default")
      (node (ref "U5") (pin "G2") (pinfunction "DQ6_G2") (pintype "bidirectional"))
    )
    (net (code "62") (name "/DDR3_D23") (class "Default")
      (node (ref "U5") (pin "H7") (pinfunction "DQ7_H7") (pintype "bidirectional"))
    )
    (net (code "63") (name "/DDR3_D24") (class "Default")
      (node (ref "U5") (pin "D7") (pinfunction "DQ8_D7") (pintype "bidirectional"))
    )
    (net (code "64") (name "/DDR3_D25") (class "Default")
      (node (ref "U5") (pin "C3") (pinfunction "DQ9_C3") (pintype "bidirectional"))
    )
    (net (code "65") (name "/DDR3_D26") (class "Default")
      (node (ref "U5") (pin "C8") (pinfunction "DQ10_C8") (pintype "bidirectional"))
    )
    (net (code "66") (name "/DDR3_D27") (class "Default")
      (node (ref "U5") (pin "C2") (pinfunction "DQ11_C2") (pintype "bidirectional"))
    )
    (net (code "67") (name "/DDR3_D28") (class "Default")
      (node (ref "U5") (pin "A7") (pinfunction "DQ12_A7") (pintype "bidirectional"))
    )
    (net (code "68") (name "/DDR3_D29") (class "Default")
      (node (ref "U5") (pin "A2") (pinfunction "DQ13_A2") (pintype "bidirectional"))
    )
    (net (code "69") (name "/DDR3_D30") (class "Default")
      (node (ref "U5") (pin "B8") (pinfunction "DQ14_B8") (pintype "bidirectional"))
    )
    (net (code "70") (name "/DDR3_D31") (class "Default")
      (node (ref "U5") (pin "A3") (pinfunction "DQ15_A3") (pintype "bidirectional"))
    )
    (net (code "71") (name "/DDR3_DM0") (class "Default")
      (node (ref "U4") (pin "E7") (pinfunction "LDM_E7") (pintype "input"))
    )
    (net (code "72") (name "/DDR3_DM1") (class "Default")
      (node (ref "U4") (pin "D3") (pinfunction "UDM_D3") (pintype "input"))
    )
    (net (code "73") (name "/DDR3_DM2") (class "Default")
      (node (ref "U5") (pin "E7") (pinfunction "LDM_E7") (pintype "input"))
    )
    (net (code "74") (name "/DDR3_DM3") (class "Default")
      (node (ref "U5") (pin "D3") (pinfunction "UDM_D3") (pintype "input"))
    )
    (net (code "75") (name "/DDR3_DQS0_N") (class "Default")
      (node (ref "U4") (pin "G3") (pinfunction "LDQS#_G3") (pintype "bidirectional"))
    )
    (net (code "76") (name "/DDR3_DQS0_P") (class "Default")
      (node (ref "U4") (pin "F3") (pinfunction "LDQS_F3") (pintype "bidirectional"))
    )
    (net (code "77") (name "/DDR3_DQS1_N") (class "Default")
      (node (ref "U4") (pin "B7") (pinfunction "UDQS#_B7") (pintype "bidirectional"))
    )
    (net (code "78") (name "/DDR3_DQS1_P") (class "Default")
      (node (ref "U4") (pin "C7") (pinfunction "UDQS_C7") (pintype "bidirectional"))
    )
    (net (code "79") (name "/DDR3_DQS2_N") (class "Default")
      (node (ref "U5") (pin "G3") (pinfunction "LDQS#_G3") (pintype "bidirectional"))
    )
    (net (code "80") (name "/DDR3_DQS2_P") (class "Default")
      (node (ref "U5") (pin "F3") (pinfunction "LDQS_F3") (pintype "bidirectional"))
    )
    (net (code "81") (name "/DDR3_DQS3_N") (class "Default")
      (node (ref "U5") (pin "B7") (pinfunction "UDQS#_B7") (pintype "bidirectional"))
    )
    (net (code "82") (name "/DDR3_DQS3_P") (class "Default")
      (node (ref "U5") (pin "C7") (pinfunction "UDQS_C7") (pintype "bidirectional"))
    )
    (net (code "83") (name "/DDR3_ODT") (class "Default")
      (node (ref "R36") (pin "1") (pinfunction "1_1") (pintype "passive"))
    )
    (net (code "84") (name "/DDR3_ODT_T") (class "Default")
      (node (ref "R36") (pin "2") (pinfunction "2_2") (pintype "passive"))
      (node (ref "U4") (pin "K1") (pinfunction "ODT_K1") (pintype "input"))
      (node (ref "U5") (pin "K1") (pinfunction "ODT_K1") (pintype "input"))
    )
    (net (code "85") (name "/DDR3_RAS") (class "Default")
      (node (ref "R19") (pin "1") (pinfunction "1_1") (pintype "passive"))
    )
    (net (code "86") (name "/DDR3_RAS_T") (class "Default")
      (node (ref "R19") (pin "2") (pinfunction "2_2") (pintype "passive"))
      (node (ref "U4") (pin "J3") (pinfunction "RAS#_J3") (pintype "input"))
      (node (ref "U5") (pin "J3") (pinfunction "RAS#_J3") (pintype "input"))
    )
    (net (code "87") (name "/DDR3_RESET") (class "Default")
      (node (ref "R16") (pin "1") (pinfunction "1_1") (pintype "passive"))
      (node (ref "U4") (pin "T2") (pinfunction "RESET#_T2") (pintype "input"))
      (node (ref "U5") (pin "T2") (pinfunction "RESET#_T2") (pintype "input"))
    )
    (net (code "88") (name "/DDR3_S0") (class "Default")
      (node (ref "R28") (pin "1") (pinfunction "1_1") (pintype "passive"))
    )
    (net (code "89") (name "/DDR3_S0_T") (class "Default")
      (node (ref "R28") (pin "2") (pinfunction "2_2") (pintype "passive"))
      (node (ref "U4") (pin "L2") (pinfunction "CS#_L2") (pintype "input"))
      (node (ref "U5") (pin "L2") (pinfunction "CS#_L2") (pintype "input"))
    )
    (net (code "90") (name "/DDR3_WE") (class "Default")
      (node (ref "R26") (pin "1") (pinfunction "1_1") (pintype "passive"))
    )
    (net (code "91") (name "/DDR3_WE_T") (class "Default")
      (node (ref "R26") (pin "2") (pinfunction "2_2") (pintype "passive"))
      (node (ref "U4") (pin "L3") (pinfunction "WE#_L3") (pintype "input"))
      (node (ref "U5") (pin "L3") (pinfunction "WE#_L3") (pintype "input"))
    )
    (net (code "92") (name "1V35") (class "Default")
      (node (ref "C10") (pin "2") (pinfunction "2_2") (pintype "passive"))
      (node (ref "C11") (pin "2") (pinfunction "2_2") (pintype "passive"))
      (node (ref "C12") (pin "2") (pinfunction "2_2") (pintype "passive"))
      (node (ref "C13") (pin "2") (pinfunction "2_2") (pintype "passive"))
      (node (ref "C14") (pin "2") (pinfunction "2_2") (pintype "passive"))
      (node (ref "C15") (pin "2") (pinfunction "2_2") (pintype "passive"))
      (node (ref "C17") (pin "2") (pinfunction "2_2") (pintype "passive"))
      (node (ref "C18") (pin "2") (pinfunction "2_2") (pintype "passive"))
      (node (ref "C19") (pin "2") (pinfunction "2_2") (pintype "passive"))
      (node (ref "C20") (pin "2") (pinfunction "2_2") (pintype "passive"))
      (node (ref "C21") (pin "2") (pinfunction "2_2") (pintype "passive"))
      (node (ref "C22") (pin "2") (pinfunction "2_2") (pintype "passive"))
      (node (ref "C23") (pin "2") (pinfunction "2_2") (pintype "passive"))
      (node (ref "C24") (pin "2") (pinfunction "2_2") (pintype "passive"))
      (node (ref "C25") (pin "2") (pinfunction "2_2") (pintype "passive"))
      (node (ref "C26") (pin "2") (pinfunction "2_2") (pintype "passive"))
      (node (ref "C27") (pin "2") (pinfunction "2_2") (pintype "passive"))
      (node (ref "C5") (pin "2") (pinfunction "2_2") (pintype "passive"))
      (node (ref "C6") (pin "2") (pinfunction "2_2") (pintype "passive"))
      (node (ref "C7") (pin "2") (pinfunction "2_2") (pintype "passive"))
      (node (ref "C8") (pin "2") (pinfunction "2_2") (pintype "passive"))
      (node (ref "C9") (pin "2") (pinfunction "2_2") (pintype "passive"))
      (node (ref "R27") (pin "2") (pinfunction "2_2") (pintype "passive"))
      (node (ref "U4") (pin "A1") (pinfunction "VDDQ_A1") (pintype "power_in"))
      (node (ref "U4") (pin "A8") (pinfunction "VDDQ_A8") (pintype "power_in"))
      (node (ref "U4") (pin "B2") (pinfunction "VDD_B2") (pintype "power_in"))
      (node (ref "U4") (pin "C1") (pinfunction "VDDQ_C1") (pintype "power_in"))
      (node (ref "U4") (pin "C9") (pinfunction "VDDQ_C9") (pintype "power_in"))
      (node (ref "U4") (pin "D2") (pinfunction "VDDQ_D2") (pintype "power_in"))
      (node (ref "U4") (pin "D9") (pinfunction "VDD_D9") (pintype "power_in"))
      (node (ref "U4") (pin "E9") (pinfunction "VDDQ_E9") (pintype "power_in"))
      (node (ref "U4") (pin "F1") (pinfunction "VDDQ_F1") (pintype "power_in"))
      (node (ref "U4") (pin "G7") (pinfunction "VDD_G7") (pintype "power_in"))
      (node (ref "U4") (pin "H2") (pinfunction "VDDQ_H2") (pintype "power_in"))
      (node (ref "U4") (pin "H9") (pinfunction "VDDQ_H9") (pintype "power_in"))
      (node (ref "U4") (pin "K2") (pinfunction "VDD_K2") (pintype "power_in"))
      (node (ref "U4") (pin "K8") (pinfunction "VDD_K8") (pintype "power_in"))
      (node (ref "U4") (pin "N1") (pinfunction "VDD_N1") (pintype "power_in"))
      (node (ref "U4") (pin "N9") (pinfunction "VDD_N9") (pintype "power_in"))
      (node (ref "U4") (pin "R1") (pinfunction "VDD_R1") (pintype "power_in"))
      (node (ref "U4") (pin "R9") (pinfunction "VDD_R9") (pintype "power_in"))
      (node (ref "U5") (pin "A1") (pinfunction "VDDQ_A1") (pintype "power_in"))
      (node (ref "U5") (pin "A8") (pinfunction "VDDQ_A8") (pintype "power_in"))
      (node (ref "U5") (pin "B2") (pinfunction "VDD_B2") (pintype "power_in"))
      (node (ref "U5") (pin "C1") (pinfunction "VDDQ_C1") (pintype "power_in"))
      (node (ref "U5") (pin "C9") (pinfunction "VDDQ_C9") (pintype "power_in"))
      (node (ref "U5") (pin "D2") (pinfunction "VDDQ_D2") (pintype "power_in"))
      (node (ref "U5") (pin "D9") (pinfunction "VDD_D9") (pintype "power_in"))
      (node (ref "U5") (pin "E9") (pinfunction "VDDQ_E9") (pintype "power_in"))
      (node (ref "U5") (pin "F1") (pinfunction "VDDQ_F1") (pintype "power_in"))
      (node (ref "U5") (pin "G7") (pinfunction "VDD_G7") (pintype "power_in"))
      (node (ref "U5") (pin "H2") (pinfunction "VDDQ_H2") (pintype "power_in"))
      (node (ref "U5") (pin "H9") (pinfunction "VDDQ_H9") (pintype "power_in"))
      (node (ref "U5") (pin "K2") (pinfunction "VDD_K2") (pintype "power_in"))
      (node (ref "U5") (pin "K8") (pinfunction "VDD_K8") (pintype "power_in"))
      (node (ref "U5") (pin "N1") (pinfunction "VDD_N1") (pintype "power_in"))
      (node (ref "U5") (pin "N9") (pinfunction "VDD_N9") (pintype "power_in"))
      (node (ref "U5") (pin "R1") (pinfunction "VDD_R1") (pintype "power_in"))
      (node (ref "U5") (pin "R9") (pinfunction "VDD_R9") (pintype "power_in"))
    )
    (net (code "93") (name "GND") (class "Default")
      (node (ref "C10") (pin "1") (pinfunction "1_1") (pintype "passive"))
      (node (ref "C11") (pin "1") (pinfunction "1_1") (pintype "passive"))
      (node (ref "C12") (pin "1") (pinfunction "1_1") (pintype "passive"))
      (node (ref "C13") (pin "1") (pinfunction "1_1") (pintype "passive"))
      (node (ref "C14") (pin "1") (pinfunction "1_1") (pintype "passive"))
      (node (ref "C15") (pin "1") (pinfunction "1_1") (pintype "passive"))
      (node (ref "C16") (pin "1") (pinfunction "1_1") (pintype "passive"))
      (node (ref "C18") (pin "1") (pinfunction "1_1") (pintype "passive"))
      (node (ref "C19") (pin "1") (pinfunction "1_1") (pintype "passive"))
      (node (ref "C20") (pin "1") (pinfunction "1_1") (pintype "passive"))
      (node (ref "C21") (pin "1") (pinfunction "1_1") (pintype "passive"))
      (node (ref "C22") (pin "1") (pinfunction "1_1") (pintype "passive"))
      (node (ref "C23") (pin "1") (pinfunction "1_1") (pintype "passive"))
      (node (ref "C24") (pin "1") (pinfunction "1_1") (pintype "passive"))
      (node (ref "C25") (pin "1") (pinfunction "1_1") (pintype "passive"))
      (node (ref "C26") (pin "1") (pinfunction "1_1") (pintype "passive"))
      (node (ref "C27") (pin "1") (pinfunction "1_1") (pintype "passive"))
      (node (ref "C28") (pin "1") (pinfunction "1_1") (pintype "passive"))
      (node (ref "C4") (pin "1") (pinfunction "1_1") (pintype "passive"))
      (node (ref "C6") (pin "1") (pinfunction "1_1") (pintype "passive"))
      (node (ref "C7") (pin "1") (pinfunction "1_1") (pintype "passive"))
      (node (ref "C8") (pin "1") (pinfunction "1_1") (pintype "passive"))
      (node (ref "C9") (pin "1") (pinfunction "1_1") (pintype "passive"))
      (node (ref "R16") (pin "2") (pinfunction "2_2") (pintype "passive"))
      (node (ref "R17") (pin "2") (pinfunction "2_2") (pintype "passive"))
      (node (ref "R18") (pin "2") (pinfunction "2_2") (pintype "passive"))
      (node (ref "R35") (pin "1") (pinfunction "1_1") (pintype "passive"))
      (node (ref "U4") (pin "A9") (pinfunction "VSS_A9") (pintype "power_in"))
      (node (ref "U4") (pin "B1") (pinfunction "VSSQ_B1") (pintype "power_in"))
      (node (ref "U4") (pin "B3") (pinfunction "VSS_B3") (pintype "power_in"))
      (node (ref "U4") (pin "B9") (pinfunction "VSSQ_B9") (pintype "power_in"))
      (node (ref "U4") (pin "D1") (pinfunction "VSSQ_D1") (pintype "power_in"))
      (node (ref "U4") (pin "D8") (pinfunction "VSSQ_D8") (pintype "power_in"))
      (node (ref "U4") (pin "E1") (pinfunction "VSS_E1") (pintype "power_in"))
      (node (ref "U4") (pin "E2") (pinfunction "VSSQ_E2") (pintype "power_in"))
      (node (ref "U4") (pin "E8") (pinfunction "VSSQ_E8") (pintype "power_in"))
      (node (ref "U4") (pin "F9") (pinfunction "VSSQ_F9") (pintype "power_in"))
      (node (ref "U4") (pin "G1") (pinfunction "VSSQ_G1") (pintype "power_in"))
      (node (ref "U4") (pin "G8") (pinfunction "VSS_G8") (pintype "power_in"))
      (node (ref "U4") (pin "G9") (pinfunction "VSSQ_G9") (pintype "power_in"))
      (node (ref "U4") (pin "J2") (pinfunction "VSS_J2") (pintype "power_in"))
      (node (ref "U4") (pin "J8") (pinfunction "VSS_J8") (pintype "power_in"))
      (node (ref "U4") (pin "M1") (pinfunction "VSS_M1") (pintype "power_in"))
      (node (ref "U4") (pin "M9") (pinfunction "VSS_M9") (pintype "power_in"))
      (node (ref "U4") (pin "P1") (pinfunction "VSS_P1") (pintype "power_in"))
      (node (ref "U4") (pin "P9") (pinfunction "VSS_P9") (pintype "power_in"))
      (node (ref "U4") (pin "T1") (pinfunction "VSS_T1") (pintype "power_in"))
      (node (ref "U4") (pin "T9") (pinfunction "VSS_T9") (pintype "power_in"))
      (node (ref "U5") (pin "A9") (pinfunction "VSS_A9") (pintype "power_in"))
      (node (ref "U5") (pin "B1") (pinfunction "VSSQ_B1") (pintype "power_in"))
      (node (ref "U5") (pin "B3") (pinfunction "VSS_B3") (pintype "power_in"))
      (node (ref "U5") (pin "B9") (pinfunction "VSSQ_B9") (pintype "power_in"))
      (node (ref "U5") (pin "D1") (pinfunction "VSSQ_D1") (pintype "power_in"))
      (node (ref "U5") (pin "D8") (pinfunction "VSSQ_D8") (pintype "power_in"))
      (node (ref "U5") (pin "E1") (pinfunction "VSS_E1") (pintype "power_in"))
      (node (ref "U5") (pin "E2") (pinfunction "VSSQ_E2") (pintype "power_in"))
      (node (ref "U5") (pin "E8") (pinfunction "VSSQ_E8") (pintype "power_in"))
      (node (ref "U5") (pin "F9") (pinfunction "VSSQ_F9") (pintype "power_in"))
      (node (ref "U5") (pin "G1") (pinfunction "VSSQ_G1") (pintype "power_in"))
      (node (ref "U5") (pin "G8") (pinfunction "VSS_G8") (pintype "power_in"))
      (node (ref "U5") (pin "G9") (pinfunction "VSSQ_G9") (pintype "power_in"))
      (node (ref "U5") (pin "J2") (pinfunction "VSS_J2") (pintype "power_in"))
      (node (ref "U5") (pin "J8") (pinfunction "VSS_J8") (pintype "power_in"))
      (node (ref "U5") (pin "M1") (pinfunction "VSS_M1") (pintype "power_in"))
      (node (ref "U5") (pin "M9") (pinfunction "VSS_M9") (pintype "power_in"))
      (node (ref "U5") (pin "P1") (pinfunction "VSS_P1") (pintype "power_in"))
      (node (ref "U5") (pin "P9") (pinfunction "VSS_P9") (pintype "power_in"))
      (node (ref "U5") (pin "T1") (pinfunction "VSS_T1") (pintype "power_in"))
      (node (ref "U5") (pin "T9") (pinfunction "VSS_T9") (pintype "power_in"))
    )
    (net (code "94") (name "Net-(U4A-ZQ)") (class "Default")
      (node (ref "R17") (pin "1") (pinfunction "1_1") (pintype "passive"))
      (node (ref "U4") (pin "L8") (pinfunction "ZQ_L8") (pintype "input"))
    )
    (net (code "95") (name "Net-(U5A-ZQ)") (class "Default")
      (node (ref "R18") (pin "1") (pinfunction "1_1") (pintype "passive"))
      (node (ref "U5") (pin "L8") (pinfunction "ZQ_L8") (pintype "input"))
    )
    (net (code "96") (name "VTTREF") (class "Default")
      (node (ref "C16") (pin "2") (pinfunction "2_2") (pintype "passive"))
      (node (ref "C17") (pin "1") (pinfunction "1_1") (pintype "passive"))
      (node (ref "C28") (pin "2") (pinfunction "2_2") (pintype "passive"))
      (node (ref "C4") (pin "2") (pinfunction "2_2") (pintype "passive"))
      (node (ref "C5") (pin "1") (pinfunction "1_1") (pintype "passive"))
      (node (ref "R27") (pin "1") (pinfunction "1_1") (pintype "passive"))
      (node (ref "R35") (pin "2") (pinfunction "2_2") (pintype "passive"))
      (node (ref "U4") (pin "H1") (pinfunction "VREFDQ_H1") (pintype "input"))
      (node (ref "U4") (pin "M8") (pinfunction "VREFCA_M8") (pintype "input"))
      (node (ref "U5") (pin "H1") (pinfunction "VREFDQ_H1") (pintype "input"))
      (node (ref "U5") (pin "M8") (pinfunction "VREFCA_M8") (pintype "input"))
    )
    (net (code "97") (name "unconnected-(U4C-NC-PadJ1)") (class "Default")
      (node (ref "U4") (pin "J1") (pinfunction "NC_J1") (pintype "passive+no_connect"))
    )
    (net (code "98") (name "unconnected-(U4C-NC-PadJ9)") (class "Default")
      (node (ref "U4") (pin "J9") (pinfunction "NC_J9") (pintype "passive+no_connect"))
    )
    (net (code "99") (name "unconnected-(U4C-NC-PadL1)") (class "Default")
      (node (ref "U4") (pin "L1") (pinfunction "NC_L1") (pintype "passive+no_connect"))
    )
    (net (code "100") (name "unconnected-(U4C-NC-PadL9)") (class "Default")
      (node (ref "U4") (pin "L9") (pinfunction "NC_L9") (pintype "passive+no_connect"))
    )
    (net (code "101") (name "unconnected-(U4C-NC-PadM7)") (class "Default")
      (node (ref "U4") (pin "M7") (pinfunction "NC_M7") (pintype "passive+no_connect"))
    )
    (net (code "102") (name "unconnected-(U4C-NC-PadT3)") (class "Default")
      (node (ref "U4") (pin "T3") (pinfunction "NC_T3") (pintype "passive+no_connect"))
    )
    (net (code "103") (name "unconnected-(U4C-NC-PadT7)") (class "Default")
      (node (ref "U4") (pin "T7") (pinfunction "NC_T7") (pintype "passive+no_connect"))
    )
    (net (code "104") (name "unconnected-(U5C-NC-PadJ1)") (class "Default")
      (node (ref "U5") (pin "J1") (pinfunction "NC_J1") (pintype "passive+no_connect"))
    )
    (net (code "105") (name "unconnected-(U5C-NC-PadJ9)") (class "Default")
      (node (ref "U5") (pin "J9") (pinfunction "NC_J9") (pintype "passive+no_connect"))
    )
    (net (code "106") (name "unconnected-(U5C-NC-PadL1)") (class "Default")
      (node (ref "U5") (pin "L1") (pinfunction "NC_L1") (pintype "passive+no_connect"))
    )
    (net (code "107") (name "unconnected-(U5C-NC-PadL9)") (class "Default")
      (node (ref "U5") (pin "L9") (pinfunction "NC_L9") (pintype "passive+no_connect"))
    )
    (net (code "108") (name "unconnected-(U5C-NC-PadM7)") (class "Default")
      (node (ref "U5") (pin "M7") (pinfunction "NC_M7") (pintype "passive+no_connect"))
    )
    (net (code "109") (name "unconnected-(U5C-NC-PadT3)") (class "Default")
      (node (ref "U5") (pin "T3") (pinfunction "NC_T3") (pintype "passive+no_connect"))
    )
    (net (code "110") (name "unconnected-(U5C-NC-PadT7)") (class "Default")
      (node (ref "U5") (pin "T7") (pinfunction "NC_T7") (pintype "passive+no_connect"))
    )
  )
)
